# AdControl.net
KiCad netlist of a schematic drawn in Altium Designer
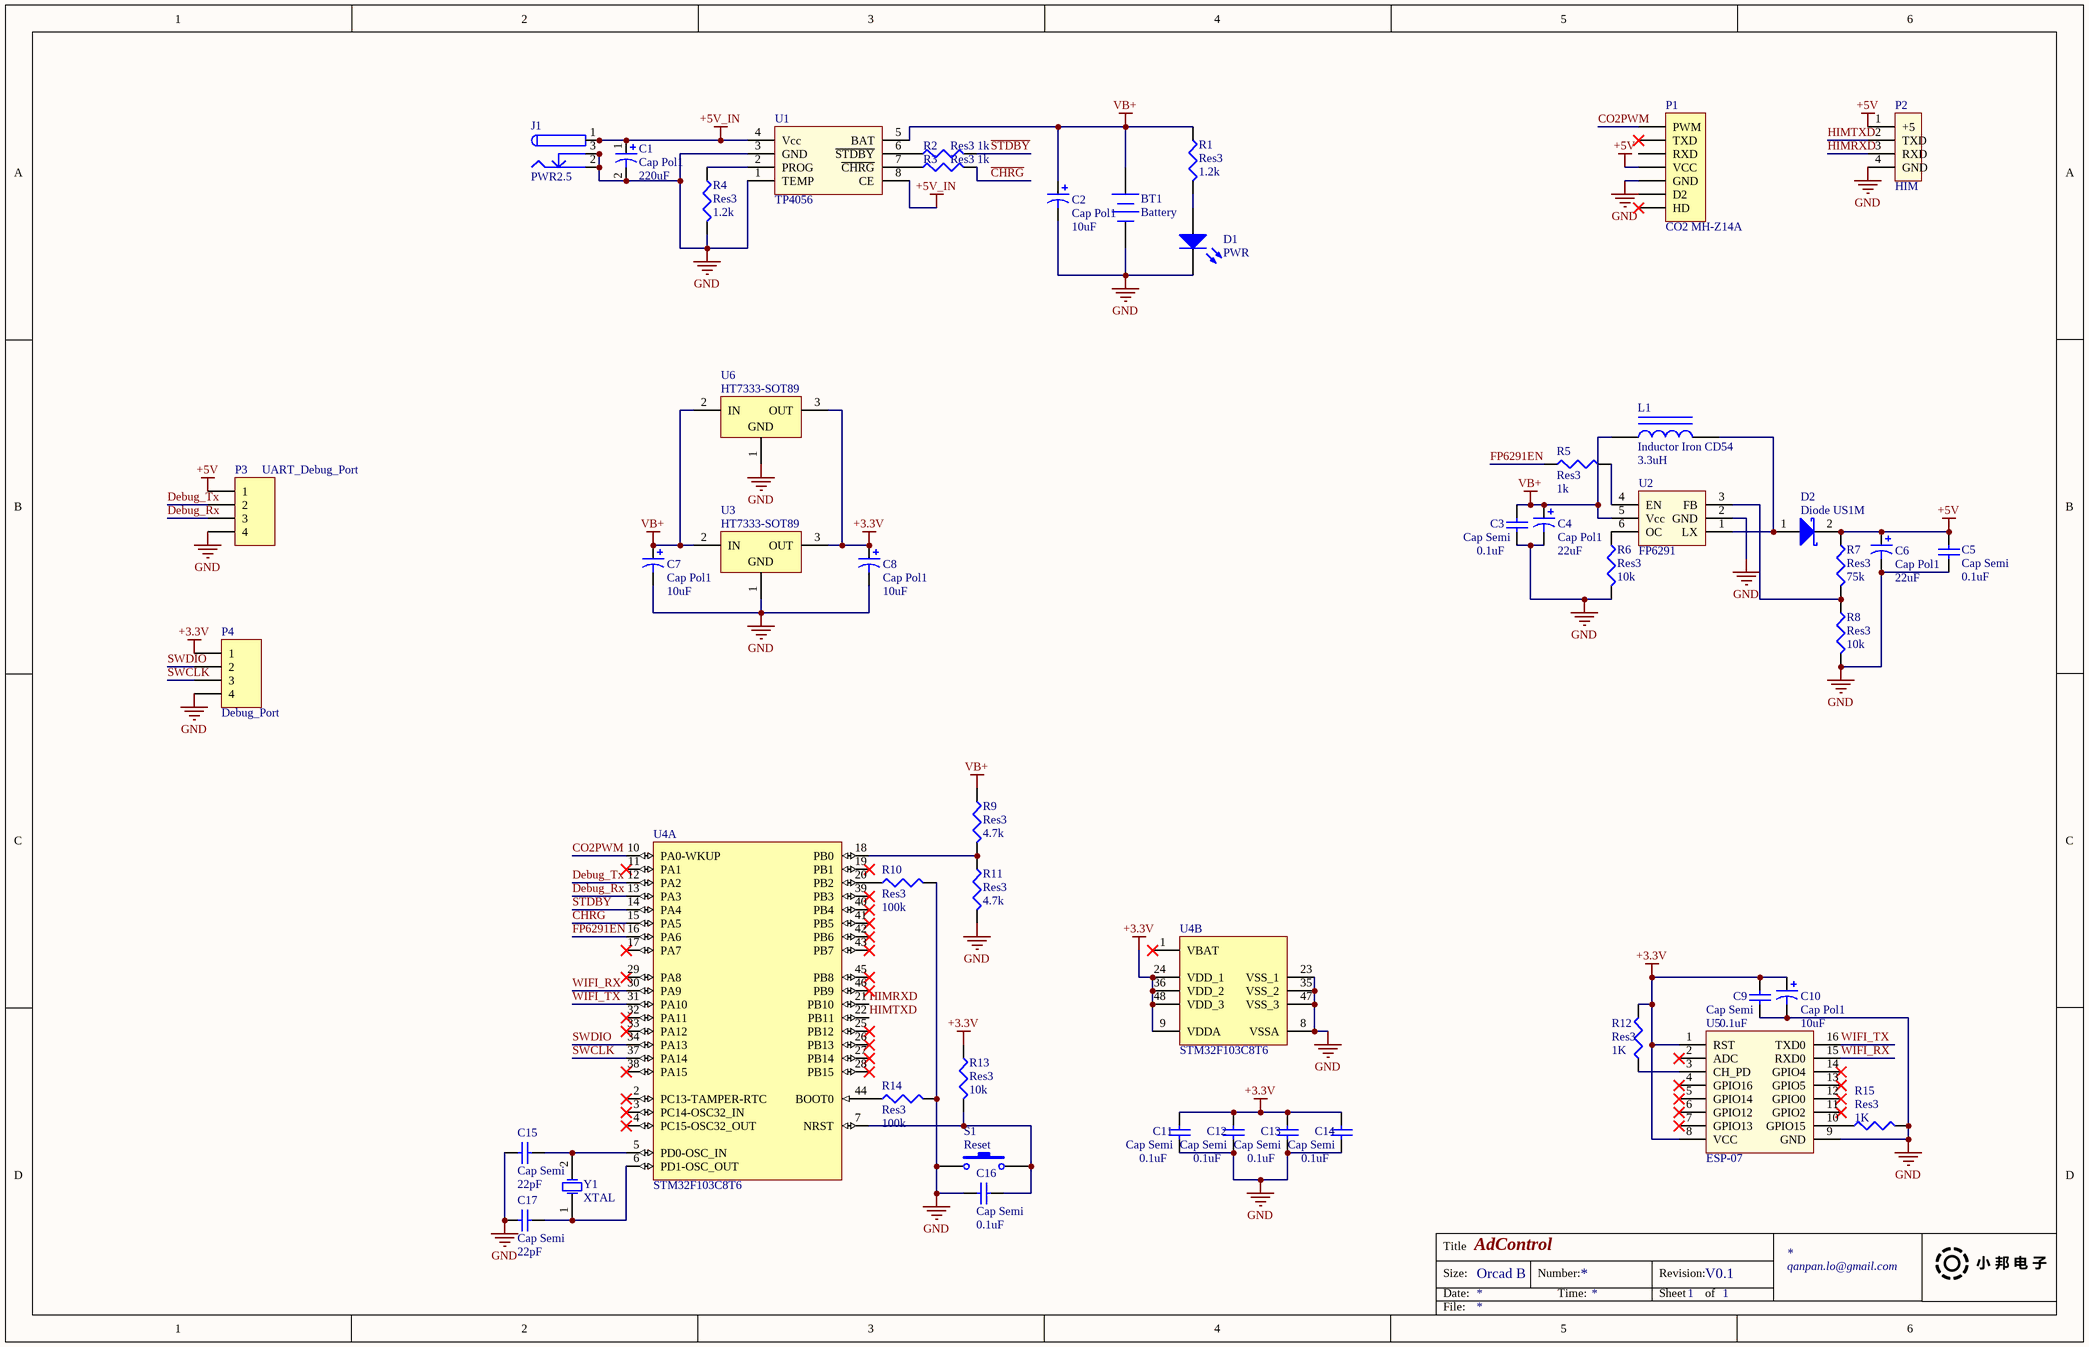
[diagram p0: AdControl.SchDoc]

(export (version "E")
  (design (tool "Eeschema 10.0.6"))
  (components
    (comp (ref "BT1")
      (value "Battery")
      (footprint "KF3.96_2P")
      (description "Multicell Battery")
      (fields (field (name "PUBLISHER") "Altium Limited"))
      (libsource (lib "Miscellaneous Devices") (part "Battery"))
    )
    (comp (ref "C1")
      (value "Cap Pol1")
      (footprint "CAP_6.3*5.4MM")
      (description "Polarized Capacitor (Radial)")
      (fields (field (name "ALTIUM_VALUE") "220uF") (field (name "PUBLISHER") "Altium Limited"))
      (libsource (lib "") (part "Cap Pol1_1"))
    )
    (comp (ref "C2")
      (value "Cap Pol1")
      (footprint "Cap_5*4mm")
      (description "Polarized Capacitor (Radial)")
      (fields (field (name "ALTIUM_VALUE") "10uF") (field (name "PUBLISHER") "Altium Limited"))
      (libsource (lib "Miscellaneous Devices") (part "Cap Pol1"))
    )
    (comp (ref "C3")
      (value "Cap Semi")
      (footprint "6-0805_N")
      (description "Capacitor (Semiconductor SIM Model)")
      (fields (field (name "ALTIUM_VALUE") "0.1uF") (field (name "PUBLISHER") "Altium Limited"))
      (libsource (lib "Miscellaneous Devices") (part "Cap Semi"))
    )
    (comp (ref "C4")
      (value "Cap Pol1")
      (footprint "Cap_5*4mm")
      (description "Polarized Capacitor (Radial)")
      (fields (field (name "ALTIUM_VALUE") "22uF") (field (name "PUBLISHER") "Altium Limited"))
      (libsource (lib "Miscellaneous Devices") (part "Cap Pol1"))
    )
    (comp (ref "C5")
      (value "Cap Semi")
      (footprint "6-0805_N")
      (description "Capacitor (Semiconductor SIM Model)")
      (fields (field (name "ALTIUM_VALUE") "0.1uF") (field (name "PUBLISHER") "Altium Limited"))
      (libsource (lib "Miscellaneous Devices") (part "Cap Semi"))
    )
    (comp (ref "C6")
      (value "Cap Pol1")
      (footprint "Cap_5*4mm")
      (description "Polarized Capacitor (Radial)")
      (fields (field (name "ALTIUM_VALUE") "22uF") (field (name "PUBLISHER") "Altium Limited"))
      (libsource (lib "Miscellaneous Devices") (part "Cap Pol1"))
    )
    (comp (ref "C7")
      (value "Cap Pol1")
      (footprint "Cap_5*4mm")
      (description "Polarized Capacitor (Radial)")
      (fields (field (name "ALTIUM_VALUE") "10uF") (field (name "PUBLISHER") "Altium Limited"))
      (libsource (lib "Miscellaneous Devices") (part "Cap Pol1"))
    )
    (comp (ref "C8")
      (value "Cap Pol1")
      (footprint "Cap_5*4mm")
      (description "Polarized Capacitor (Radial)")
      (fields (field (name "ALTIUM_VALUE") "10uF") (field (name "PUBLISHER") "Altium Limited"))
      (libsource (lib "Miscellaneous Devices") (part "Cap Pol1"))
    )
    (comp (ref "C9")
      (value "Cap Semi")
      (footprint "6-0805_N")
      (description "Capacitor (Semiconductor SIM Model)")
      (fields (field (name "ALTIUM_VALUE") "0.1uF") (field (name "PUBLISHER") "Altium Limited"))
      (libsource (lib "Miscellaneous Devices") (part "Cap Semi"))
    )
    (comp (ref "C10")
      (value "Cap Pol1")
      (footprint "Cap_5*4mm")
      (description "Polarized Capacitor (Radial)")
      (fields (field (name "ALTIUM_VALUE") "10uF") (field (name "PUBLISHER") "Altium Limited"))
      (libsource (lib "Miscellaneous Devices") (part "Cap Pol1"))
    )
    (comp (ref "C11")
      (value "Cap Semi")
      (footprint "6-0805_N")
      (description "Capacitor (Semiconductor SIM Model)")
      (fields (field (name "ALTIUM_VALUE") "0.1uF") (field (name "PUBLISHER") "Altium Limited"))
      (libsource (lib "Miscellaneous Devices") (part "Cap Semi"))
    )
    (comp (ref "C12")
      (value "Cap Semi")
      (footprint "6-0805_N")
      (description "Capacitor (Semiconductor SIM Model)")
      (fields (field (name "ALTIUM_VALUE") "0.1uF") (field (name "PUBLISHER") "Altium Limited"))
      (libsource (lib "Miscellaneous Devices") (part "Cap Semi"))
    )
    (comp (ref "C13")
      (value "Cap Semi")
      (footprint "6-0805_N")
      (description "Capacitor (Semiconductor SIM Model)")
      (fields (field (name "ALTIUM_VALUE") "0.1uF") (field (name "PUBLISHER") "Altium Limited"))
      (libsource (lib "Miscellaneous Devices") (part "Cap Semi"))
    )
    (comp (ref "C14")
      (value "Cap Semi")
      (footprint "6-0805_N")
      (description "Capacitor (Semiconductor SIM Model)")
      (fields (field (name "ALTIUM_VALUE") "0.1uF") (field (name "PUBLISHER") "Altium Limited"))
      (libsource (lib "Miscellaneous Devices") (part "Cap Semi"))
    )
    (comp (ref "C15")
      (value "Cap Semi")
      (footprint "6-0805_N")
      (description "Capacitor (Semiconductor SIM Model)")
      (fields (field (name "ALTIUM_VALUE") "22pF") (field (name "PUBLISHER") "Altium Limited"))
      (libsource (lib "Miscellaneous Devices") (part "Cap Semi"))
    )
    (comp (ref "C16")
      (value "Cap Semi")
      (footprint "6-0805_N")
      (description "Capacitor (Semiconductor SIM Model)")
      (fields (field (name "ALTIUM_VALUE") "0.1uF") (field (name "PUBLISHER") "Altium Limited"))
      (libsource (lib "Miscellaneous Devices") (part "Cap Semi"))
    )
    (comp (ref "C17")
      (value "Cap Semi")
      (footprint "6-0805_N")
      (description "Capacitor (Semiconductor SIM Model)")
      (fields (field (name "ALTIUM_VALUE") "22pF") (field (name "PUBLISHER") "Altium Limited"))
      (libsource (lib "Miscellaneous Devices") (part "Cap Semi"))
    )
    (comp (ref "D1")
      (value "PWR")
      (footprint "6-0805_N")
      (description "Typical INFRARED GaAs LED")
      (fields (field (name "PUBLISHER") "Altium Limited"))
      (libsource (lib "Miscellaneous Devices") (part "LED0"))
    )
    (comp (ref "D2")
      (value "Diode US1M")
      (footprint "US1M")
      (description "Silicon RF Schottky Diode for Mixer Applications in the VHF/UHF Range")
      (fields (field (name "PUBLISHER") "Altium Limited"))
      (libsource (lib "Miscellaneous Devices") (part "Diode BAT17"))
    )
    (comp (ref "J1")
      (value "PWR2.5")
      (footprint "KLD-3.5-1.3mm")
      (description "Low Voltage Power Supply Connector")
      (fields (field (name "PUBLISHER") "Altium Limited"))
      (libsource (lib "Miscellaneous Connectors") (part "PWR2.5"))
    )
    (comp (ref "L1")
      (value "Inductor Iron CD54")
      (footprint "CD54_Inductor")
      (description "Magnetic-Core Inductor")
      (fields (field (name "ALTIUM_VALUE") "3.3uH") (field (name "PUBLISHER") "Altium Limited"))
      (libsource (lib "Miscellaneous Devices") (part "Inductor Iron"))
    )
    (comp (ref "P1")
      (value "CO2 MH-Z14A")
      (footprint "1.25Connector")
      (description "Header, 7-Pin")
      (fields (field (name "PUBLISHER") "Altium Limited"))
      (libsource (lib "Miscellaneous Connectors") (part "Header 7"))
    )
    (comp (ref "P2") (value "HIM") (footprint "XH2.54-4P") (libsource (lib "XH2.54") (part "XH2.54-4P")))
    (comp (ref "P3")
      (value "UART_Debug_Port")
      (footprint "HDR1X4")
      (description "Header, 4-Pin")
      (fields (field (name "PUBLISHER") "Altium Limited"))
      (libsource (lib "Miscellaneous Connectors") (part "Header 4"))
    )
    (comp (ref "P4")
      (value "Debug_Port")
      (footprint "HDR1X4")
      (description "Header, 4-Pin")
      (fields (field (name "PUBLISHER") "Altium Limited"))
      (libsource (lib "Miscellaneous Connectors") (part "Header 4"))
    )
    (comp (ref "R1")
      (value "Res3")
      (footprint "6-0805_N")
      (description "Resistor")
      (fields (field (name "ALTIUM_VALUE") "1.2k") (field (name "PUBLISHER") "Altium Limited"))
      (libsource (lib "Miscellaneous Devices") (part "Res3"))
    )
    (comp (ref "R2")
      (value "Res3")
      (footprint "6-0805_N")
      (description "Resistor")
      (fields (field (name "ALTIUM_VALUE") "1k") (field (name "PUBLISHER") "Altium Limited"))
      (libsource (lib "Miscellaneous Devices") (part "Res3"))
    )
    (comp (ref "R3")
      (value "Res3")
      (footprint "6-0805_N")
      (description "Resistor")
      (fields (field (name "ALTIUM_VALUE") "1k") (field (name "PUBLISHER") "Altium Limited"))
      (libsource (lib "Miscellaneous Devices") (part "Res3"))
    )
    (comp (ref "R4")
      (value "Res3")
      (footprint "6-0805_N")
      (description "Resistor")
      (fields (field (name "ALTIUM_VALUE") "1.2k") (field (name "PUBLISHER") "Altium Limited"))
      (libsource (lib "Miscellaneous Devices") (part "Res3"))
    )
    (comp (ref "R5")
      (value "Res3")
      (footprint "6-0805_N")
      (description "Resistor")
      (fields (field (name "ALTIUM_VALUE") "1k") (field (name "PUBLISHER") "Altium Limited"))
      (libsource (lib "Miscellaneous Devices") (part "Res3"))
    )
    (comp (ref "R6")
      (value "Res3")
      (footprint "6-0805_N")
      (description "Resistor")
      (fields (field (name "ALTIUM_VALUE") "10k") (field (name "PUBLISHER") "Altium Limited"))
      (libsource (lib "Miscellaneous Devices") (part "Res3"))
    )
    (comp (ref "R7")
      (value "Res3")
      (footprint "6-0805_N")
      (description "Resistor")
      (fields (field (name "ALTIUM_VALUE") "75k") (field (name "PUBLISHER") "Altium Limited"))
      (libsource (lib "Miscellaneous Devices") (part "Res3"))
    )
    (comp (ref "R8")
      (value "Res3")
      (footprint "6-0805_N")
      (description "Resistor")
      (fields (field (name "ALTIUM_VALUE") "10k") (field (name "PUBLISHER") "Altium Limited"))
      (libsource (lib "Miscellaneous Devices") (part "Res3"))
    )
    (comp (ref "R9")
      (value "Res3")
      (footprint "6-0805_N")
      (description "Resistor")
      (fields (field (name "ALTIUM_VALUE") "4.7k") (field (name "PUBLISHER") "Altium Limited"))
      (libsource (lib "Miscellaneous Devices") (part "Res3"))
    )
    (comp (ref "R10")
      (value "Res3")
      (footprint "6-0805_N")
      (description "Resistor")
      (fields (field (name "ALTIUM_VALUE") "100k") (field (name "PUBLISHER") "Altium Limited"))
      (libsource (lib "Miscellaneous Devices") (part "Res3"))
    )
    (comp (ref "R11")
      (value "Res3")
      (footprint "6-0805_N")
      (description "Resistor")
      (fields (field (name "ALTIUM_VALUE") "4.7k") (field (name "PUBLISHER") "Altium Limited"))
      (libsource (lib "Miscellaneous Devices") (part "Res3"))
    )
    (comp (ref "R12")
      (value "Res3")
      (footprint "6-0805_N")
      (description "Resistor")
      (fields (field (name "ALTIUM_VALUE") "1K") (field (name "PUBLISHER") "Altium Limited"))
      (libsource (lib "Miscellaneous Devices") (part "Res3"))
    )
    (comp (ref "R13")
      (value "Res3")
      (footprint "6-0805_N")
      (description "Resistor")
      (fields (field (name "ALTIUM_VALUE") "10k") (field (name "PUBLISHER") "Altium Limited"))
      (libsource (lib "Miscellaneous Devices") (part "Res3"))
    )
    (comp (ref "R14")
      (value "Res3")
      (footprint "6-0805_N")
      (description "Resistor")
      (fields (field (name "ALTIUM_VALUE") "100k") (field (name "PUBLISHER") "Altium Limited"))
      (libsource (lib "Miscellaneous Devices") (part "Res3"))
    )
    (comp (ref "R15")
      (value "Res3")
      (footprint "6-0805_N")
      (description "Resistor")
      (fields (field (name "ALTIUM_VALUE") "1K") (field (name "PUBLISHER") "Altium Limited"))
      (libsource (lib "Miscellaneous Devices") (part "Res3"))
    )
    (comp (ref "S1")
      (value "Reset")
      (footprint "SWP_PB_6.5mm")
      (description "Switch")
      (fields (field (name "PUBLISHER") "Altium Limited"))
      (libsource (lib "Miscellaneous Devices") (part "SW-PB"))
    )
    (comp (ref "U1")
      (value "TP4056")
      (footprint "Power_SOP8")
      (libsource (lib "Simon'Library") (part "TP4056"))
    )
    (comp (ref "U2")
      (value "FP6291")
      (footprint "SOT23-6L")
      (libsource (lib "Simon'Library") (part "FP6291"))
    )
    (comp (ref "U3")
      (value "HT7333-SOT89")
      (footprint "SOT89_N")
      (description "Low Power Consumption LDO, Output Voltage 3.3V, SOT89 Pkg")
      (libsource (lib "Altium Content Vault") (part "PM-REG-HT73XX-IL3"))
    )
    (comp (ref "U4")
      (value "STM32F103C8T6")
      (footprint "STM-LQFP48_L")
      (libsource (lib "Altium Content Vault") (part "MC-ARM-STM32F103X8_B-SQ48"))
    )
    (comp (ref "U5")
      (value "ESP-07")
      (footprint "ESP-07_Wifi")
      (libsource (lib "Simon'Library") (part "ESP-07_Wifi"))
    )
    (comp (ref "U6")
      (value "HT7333-SOT89")
      (footprint "SOT89_N")
      (description "Low Power Consumption LDO, Output Voltage 3.3V, SOT89 Pkg")
      (libsource (lib "Altium Content Vault") (part "PM-REG-HT73XX-IL3"))
    )
    (comp (ref "Y1")
      (value "XTAL")
      (footprint "OSC_5032_2Pin")
      (description "Crystal Oscillator")
      (fields (field (name "PUBLISHER") "Altium Limited"))
      (libsource (lib "Miscellaneous Devices") (part "XTAL"))
    )
  )
  (nets
    (net (code "1") (name "+3.3V") (class "Default")
      (node (ref "C10") (pin "1") (pinfunction "1_1") (pintype "passive"))
      (node (ref "C11") (pin "1") (pinfunction "1_1") (pintype "passive"))
      (node (ref "C12") (pin "1") (pinfunction "1_1") (pintype "passive"))
      (node (ref "C13") (pin "1") (pinfunction "1_1") (pintype "passive"))
      (node (ref "C14") (pin "1") (pinfunction "1_1") (pintype "passive"))
      (node (ref "C8") (pin "1") (pinfunction "1_1") (pintype "passive"))
      (node (ref "C9") (pin "1") (pinfunction "1_1") (pintype "passive"))
      (node (ref "P4") (pin "1") (pinfunction "1_1") (pintype "passive"))
      (node (ref "R12") (pin "2") (pinfunction "2_2") (pintype "passive"))
      (node (ref "R13") (pin "1") (pinfunction "1_1") (pintype "passive"))
      (node (ref "U3") (pin "3") (pinfunction "OUT_3") (pintype "power_in"))
      (node (ref "U4") (pin "24") (pinfunction "VDD_1_24") (pintype "power_in"))
      (node (ref "U4") (pin "36") (pinfunction "VDD_2_36") (pintype "power_in"))
      (node (ref "U4") (pin "48") (pinfunction "VDD_3_48") (pintype "power_in"))
      (node (ref "U4") (pin "9") (pinfunction "VDDA_9") (pintype "power_in"))
      (node (ref "U5") (pin "1") (pinfunction "RST_1") (pintype "passive"))
      (node (ref "U5") (pin "8") (pinfunction "VCC_8") (pintype "passive"))
      (node (ref "U6") (pin "3") (pinfunction "OUT_3") (pintype "power_in"))
    )
    (net (code "2") (name "+5V") (class "Default")
      (node (ref "C5") (pin "1") (pinfunction "1_1") (pintype "passive"))
      (node (ref "C6") (pin "1") (pinfunction "1_1") (pintype "passive"))
      (node (ref "D2") (pin "2") (pinfunction "K_2") (pintype "passive"))
      (node (ref "P1") (pin "4") (pinfunction "VCC_4") (pintype "passive"))
      (node (ref "P2") (pin "1") (pinfunction "+5_1") (pintype "passive"))
      (node (ref "P3") (pin "1") (pinfunction "1_1") (pintype "passive"))
      (node (ref "R7") (pin "1") (pinfunction "1_1") (pintype "passive"))
    )
    (net (code "3") (name "+5V_IN") (class "Default")
      (node (ref "C1") (pin "1") (pinfunction "1_1") (pintype "passive"))
      (node (ref "J1") (pin "1") (pinfunction "1_1") (pintype "power_in"))
      (node (ref "J1") (pin "1A") (pinfunction "1A_1A") (pintype "power_in"))
      (node (ref "J1") (pin "1B") (pinfunction "1B_1B") (pintype "power_in"))
      (node (ref "U1") (pin "4") (pinfunction "Vcc_4") (pintype "passive"))
      (node (ref "U1") (pin "8") (pinfunction "CE_8") (pintype "passive"))
    )
    (net (code "4") (name "/CO2PWM") (class "Default")
      (node (ref "P1") (pin "1") (pinfunction "PWM_1") (pintype "passive"))
      (node (ref "U4") (pin "10") (pinfunction "PA0-WKUP_10") (pintype "bidirectional"))
    )
    (net (code "5") (name "/Debug_Rx") (class "Default")
      (node (ref "P3") (pin "3") (pinfunction "3_3") (pintype "passive"))
      (node (ref "U4") (pin "13") (pinfunction "PA3_13") (pintype "bidirectional"))
    )
    (net (code "6") (name "/Debug_Tx") (class "Default")
      (node (ref "P3") (pin "2") (pinfunction "2_2") (pintype "passive"))
      (node (ref "U4") (pin "12") (pinfunction "PA2_12") (pintype "bidirectional"))
    )
    (net (code "7") (name "/FP6291EN") (class "Default")
      (node (ref "R5") (pin "1") (pinfunction "1_1") (pintype "passive"))
      (node (ref "U4") (pin "16") (pinfunction "PA6_16") (pintype "bidirectional"))
    )
    (net (code "8") (name "/HIMRXD") (class "Default")
      (node (ref "P2") (pin "3") (pinfunction "RXD_3") (pintype "passive"))
      (node (ref "U4") (pin "21") (pinfunction "PB10_21") (pintype "bidirectional"))
    )
    (net (code "9") (name "/HIMTXD") (class "Default")
      (node (ref "P2") (pin "2") (pinfunction "TXD_2") (pintype "passive"))
      (node (ref "U4") (pin "22") (pinfunction "PB11_22") (pintype "bidirectional"))
    )
    (net (code "10") (name "/SWCLK") (class "Default")
      (node (ref "P4") (pin "3") (pinfunction "3_3") (pintype "passive"))
      (node (ref "U4") (pin "37") (pinfunction "PA14_37") (pintype "bidirectional"))
    )
    (net (code "11") (name "/SWDIO") (class "Default")
      (node (ref "P4") (pin "2") (pinfunction "2_2") (pintype "passive"))
      (node (ref "U4") (pin "34") (pinfunction "PA13_34") (pintype "bidirectional"))
    )
    (net (code "12") (name "/WIFI_RX") (class "Default")
      (node (ref "U4") (pin "30") (pinfunction "PA9_30") (pintype "bidirectional"))
      (node (ref "U5") (pin "15") (pinfunction "RXD0_15") (pintype "passive"))
    )
    (net (code "13") (name "/WIFI_TX") (class "Default")
      (node (ref "U4") (pin "31") (pinfunction "PA10_31") (pintype "bidirectional"))
      (node (ref "U5") (pin "16") (pinfunction "TXD0_16") (pintype "passive"))
    )
    (net (code "14") (name "/~{CHRG}") (class "Default")
      (node (ref "R3") (pin "2") (pinfunction "2_2") (pintype "passive"))
      (node (ref "U4") (pin "15") (pinfunction "PA5_15") (pintype "bidirectional"))
    )
    (net (code "15") (name "/~{STDBY}") (class "Default")
      (node (ref "R2") (pin "2") (pinfunction "2_2") (pintype "passive"))
      (node (ref "U4") (pin "14") (pinfunction "PA4_14") (pintype "bidirectional"))
    )
    (net (code "16") (name "GND") (class "Default")
      (node (ref "BT1") (pin "2") (pinfunction "-_2") (pintype "passive"))
      (node (ref "C1") (pin "2") (pinfunction "2_2") (pintype "passive"))
      (node (ref "C10") (pin "2") (pinfunction "2_2") (pintype "passive"))
      (node (ref "C11") (pin "2") (pinfunction "2_2") (pintype "passive"))
      (node (ref "C12") (pin "2") (pinfunction "2_2") (pintype "passive"))
      (node (ref "C13") (pin "2") (pinfunction "2_2") (pintype "passive"))
      (node (ref "C14") (pin "2") (pinfunction "2_2") (pintype "passive"))
      (node (ref "C15") (pin "2") (pinfunction "2_2") (pintype "passive"))
      (node (ref "C16") (pin "1") (pinfunction "1_1") (pintype "passive"))
      (node (ref "C17") (pin "2") (pinfunction "2_2") (pintype "passive"))
      (node (ref "C2") (pin "2") (pinfunction "2_2") (pintype "passive"))
      (node (ref "C3") (pin "2") (pinfunction "2_2") (pintype "passive"))
      (node (ref "C4") (pin "2") (pinfunction "2_2") (pintype "passive"))
      (node (ref "C5") (pin "2") (pinfunction "2_2") (pintype "passive"))
      (node (ref "C6") (pin "2") (pinfunction "2_2") (pintype "passive"))
      (node (ref "C7") (pin "2") (pinfunction "2_2") (pintype "passive"))
      (node (ref "C8") (pin "2") (pinfunction "2_2") (pintype "passive"))
      (node (ref "C9") (pin "2") (pinfunction "2_2") (pintype "passive"))
      (node (ref "D1") (pin "2") (pinfunction "K_2") (pintype "passive"))
      (node (ref "J1") (pin "2") (pinfunction "2_2") (pintype "power_in"))
      (node (ref "J1") (pin "2A") (pinfunction "2A_2A") (pintype "power_in"))
      (node (ref "J1") (pin "2B") (pinfunction "2B_2B") (pintype "power_in"))
      (node (ref "J1") (pin "3") (pinfunction "3_3") (pintype "power_in"))
      (node (ref "J1") (pin "3A") (pinfunction "3A_3A") (pintype "power_in"))
      (node (ref "J1") (pin "3B") (pinfunction "3B_3B") (pintype "power_in"))
      (node (ref "P1") (pin "5") (pinfunction "GND_5") (pintype "passive"))
      (node (ref "P2") (pin "4") (pinfunction "GND_4") (pintype "passive"))
      (node (ref "P3") (pin "4") (pinfunction "4_4") (pintype "passive"))
      (node (ref "P4") (pin "4") (pinfunction "4_4") (pintype "passive"))
      (node (ref "R10") (pin "2") (pinfunction "2_2") (pintype "passive"))
      (node (ref "R11") (pin "2") (pinfunction "2_2") (pintype "passive"))
      (node (ref "R14") (pin "2") (pinfunction "2_2") (pintype "passive"))
      (node (ref "R15") (pin "2") (pinfunction "2_2") (pintype "passive"))
      (node (ref "R4") (pin "2") (pinfunction "2_2") (pintype "passive"))
      (node (ref "R6") (pin "2") (pinfunction "2_2") (pintype "passive"))
      (node (ref "R8") (pin "2") (pinfunction "2_2") (pintype "passive"))
      (node (ref "S1") (pin "1") (pinfunction "1_1") (pintype "passive"))
      (node (ref "U1") (pin "1") (pinfunction "TEMP_1") (pintype "passive"))
      (node (ref "U1") (pin "3") (pinfunction "GND_3") (pintype "passive"))
      (node (ref "U2") (pin "2") (pinfunction "GND_2") (pintype "passive"))
      (node (ref "U3") (pin "1") (pinfunction "GND_1") (pintype "power_in"))
      (node (ref "U4") (pin "23") (pinfunction "VSS_1_23") (pintype "power_in"))
      (node (ref "U4") (pin "35") (pinfunction "VSS_2_35") (pintype "power_in"))
      (node (ref "U4") (pin "47") (pinfunction "VSS_3_47") (pintype "power_in"))
      (node (ref "U4") (pin "8") (pinfunction "VSSA_8") (pintype "power_in"))
      (node (ref "U5") (pin "9") (pinfunction "GND_9") (pintype "passive"))
      (node (ref "U6") (pin "1") (pinfunction "GND_1") (pintype "power_in"))
    )
    (net (code "17") (name "Net-(D1-A)") (class "Default")
      (node (ref "D1") (pin "1") (pinfunction "A_1") (pintype "passive"))
      (node (ref "R1") (pin "2") (pinfunction "2_2") (pintype "passive"))
    )
    (net (code "18") (name "Net-(D2-A)") (class "Default")
      (node (ref "D2") (pin "1") (pinfunction "A_1") (pintype "passive"))
      (node (ref "L1") (pin "2") (pinfunction "2_2") (pintype "passive"))
      (node (ref "U2") (pin "1") (pinfunction "LX_1") (pintype "passive"))
    )
    (net (code "19") (name "Net-(U1-PROG)") (class "Default")
      (node (ref "R4") (pin "1") (pinfunction "1_1") (pintype "passive"))
      (node (ref "U1") (pin "2") (pinfunction "PROG_2") (pintype "passive"))
    )
    (net (code "20") (name "Net-(U1-~{CHRG})") (class "Default")
      (node (ref "R3") (pin "1") (pinfunction "1_1") (pintype "passive"))
      (node (ref "U1") (pin "7") (pinfunction "~{CHRG}_7") (pintype "passive"))
    )
    (net (code "21") (name "Net-(U1-~{STDBY})") (class "Default")
      (node (ref "R2") (pin "1") (pinfunction "1_1") (pintype "passive"))
      (node (ref "U1") (pin "6") (pinfunction "~{STDBY}_6") (pintype "passive"))
    )
    (net (code "22") (name "Net-(U2-EN)") (class "Default")
      (node (ref "R5") (pin "2") (pinfunction "2_2") (pintype "passive"))
      (node (ref "U2") (pin "4") (pinfunction "EN_4") (pintype "passive"))
    )
    (net (code "23") (name "Net-(U2-FB)") (class "Default")
      (node (ref "R7") (pin "2") (pinfunction "2_2") (pintype "passive"))
      (node (ref "R8") (pin "1") (pinfunction "1_1") (pintype "passive"))
      (node (ref "U2") (pin "3") (pinfunction "FB_3") (pintype "passive"))
    )
    (net (code "24") (name "Net-(U2-OC)") (class "Default")
      (node (ref "R6") (pin "1") (pinfunction "1_1") (pintype "passive"))
      (node (ref "U2") (pin "6") (pinfunction "OC_6") (pintype "passive"))
    )
    (net (code "25") (name "Net-(U4A-BOOT0)") (class "Default")
      (node (ref "R14") (pin "1") (pinfunction "1_1") (pintype "passive"))
      (node (ref "U4") (pin "44") (pinfunction "BOOT0_44") (pintype "input"))
    )
    (net (code "26") (name "Net-(U4A-NRST)") (class "Default")
      (node (ref "C16") (pin "2") (pinfunction "2_2") (pintype "passive"))
      (node (ref "R13") (pin "2") (pinfunction "2_2") (pintype "passive"))
      (node (ref "S1") (pin "2") (pinfunction "2_2") (pintype "passive"))
      (node (ref "U4") (pin "7") (pinfunction "NRST_7") (pintype "bidirectional"))
    )
    (net (code "27") (name "Net-(U4A-PB0)") (class "Default")
      (node (ref "R11") (pin "1") (pinfunction "1_1") (pintype "passive"))
      (node (ref "R9") (pin "2") (pinfunction "2_2") (pintype "passive"))
      (node (ref "U4") (pin "18") (pinfunction "PB0_18") (pintype "bidirectional"))
    )
    (net (code "28") (name "Net-(U4A-PB2)") (class "Default")
      (node (ref "R10") (pin "1") (pinfunction "1_1") (pintype "passive"))
      (node (ref "U4") (pin "20") (pinfunction "PB2_20") (pintype "bidirectional"))
    )
    (net (code "29") (name "Net-(U4A-PD0-OSC_IN)") (class "Default")
      (node (ref "C15") (pin "1") (pinfunction "1_1") (pintype "passive"))
      (node (ref "U4") (pin "5") (pinfunction "PD0-OSC_IN_5") (pintype "bidirectional"))
      (node (ref "Y1") (pin "2") (pinfunction "OSC2_2") (pintype "passive"))
    )
    (net (code "30") (name "Net-(U4A-PD1-OSC_OUT)") (class "Default")
      (node (ref "C17") (pin "1") (pinfunction "1_1") (pintype "passive"))
      (node (ref "U4") (pin "6") (pinfunction "PD1-OSC_OUT_6") (pintype "bidirectional"))
      (node (ref "Y1") (pin "1") (pinfunction "OSC1_1") (pintype "passive"))
    )
    (net (code "31") (name "Net-(U5-CH_PD)") (class "Default")
      (node (ref "R12") (pin "1") (pinfunction "1_1") (pintype "passive"))
      (node (ref "U5") (pin "3") (pinfunction "CH_PD_3") (pintype "passive"))
    )
    (net (code "32") (name "Net-(U5-GPIO15)") (class "Default")
      (node (ref "R15") (pin "1") (pinfunction "1_1") (pintype "passive"))
      (node (ref "U5") (pin "10") (pinfunction "GPIO15_10") (pintype "passive"))
    )
    (net (code "33") (name "VB+") (class "Default")
      (node (ref "BT1") (pin "1") (pinfunction "+_1") (pintype "passive"))
      (node (ref "C2") (pin "1") (pinfunction "1_1") (pintype "passive"))
      (node (ref "C3") (pin "1") (pinfunction "1_1") (pintype "passive"))
      (node (ref "C4") (pin "1") (pinfunction "1_1") (pintype "passive"))
      (node (ref "C7") (pin "1") (pinfunction "1_1") (pintype "passive"))
      (node (ref "L1") (pin "1") (pinfunction "1_1") (pintype "passive"))
      (node (ref "R1") (pin "1") (pinfunction "1_1") (pintype "passive"))
      (node (ref "R9") (pin "1") (pinfunction "1_1") (pintype "passive"))
      (node (ref "U1") (pin "5") (pinfunction "BAT_5") (pintype "passive"))
      (node (ref "U2") (pin "5") (pinfunction "Vcc_5") (pintype "passive"))
      (node (ref "U3") (pin "2") (pinfunction "IN_2") (pintype "power_in"))
      (node (ref "U6") (pin "2") (pinfunction "IN_2") (pintype "power_in"))
    )
    (net (code "34") (name "unconnected-(P1-D2-Pad6)") (class "Default")
      (node (ref "P1") (pin "6") (pinfunction "D2_6") (pintype "passive"))
    )
    (net (code "35") (name "unconnected-(P1-HD-Pad7)") (class "Default")
      (node (ref "P1") (pin "7") (pinfunction "HD_7") (pintype "passive+no_connect"))
    )
    (net (code "36") (name "unconnected-(P1-RXD-Pad3)") (class "Default")
      (node (ref "P1") (pin "3") (pinfunction "RXD_3") (pintype "passive"))
    )
    (net (code "37") (name "unconnected-(P1-TXD-Pad2)") (class "Default")
      (node (ref "P1") (pin "2") (pinfunction "TXD_2") (pintype "passive+no_connect"))
    )
    (net (code "38") (name "unconnected-(U4A-PA1-Pad11)") (class "Default")
      (node (ref "U4") (pin "11") (pinfunction "PA1_11") (pintype "bidirectional+no_connect"))
    )
    (net (code "39") (name "unconnected-(U4A-PA7-Pad17)") (class "Default")
      (node (ref "U4") (pin "17") (pinfunction "PA7_17") (pintype "bidirectional+no_connect"))
    )
    (net (code "40") (name "unconnected-(U4A-PA8-Pad29)") (class "Default")
      (node (ref "U4") (pin "29") (pinfunction "PA8_29") (pintype "bidirectional+no_connect"))
    )
    (net (code "41") (name "unconnected-(U4A-PA11-Pad32)") (class "Default")
      (node (ref "U4") (pin "32") (pinfunction "PA11_32") (pintype "bidirectional+no_connect"))
    )
    (net (code "42") (name "unconnected-(U4A-PA12-Pad33)") (class "Default")
      (node (ref "U4") (pin "33") (pinfunction "PA12_33") (pintype "bidirectional+no_connect"))
    )
    (net (code "43") (name "unconnected-(U4A-PA15-Pad38)") (class "Default")
      (node (ref "U4") (pin "38") (pinfunction "PA15_38") (pintype "bidirectional+no_connect"))
    )
    (net (code "44") (name "unconnected-(U4A-PB1-Pad19)") (class "Default")
      (node (ref "U4") (pin "19") (pinfunction "PB1_19") (pintype "bidirectional+no_connect"))
    )
    (net (code "45") (name "unconnected-(U4A-PB3-Pad39)") (class "Default")
      (node (ref "U4") (pin "39") (pinfunction "PB3_39") (pintype "bidirectional+no_connect"))
    )
    (net (code "46") (name "unconnected-(U4A-PB4-Pad40)") (class "Default")
      (node (ref "U4") (pin "40") (pinfunction "PB4_40") (pintype "bidirectional+no_connect"))
    )
    (net (code "47") (name "unconnected-(U4A-PB5-Pad41)") (class "Default")
      (node (ref "U4") (pin "41") (pinfunction "PB5_41") (pintype "bidirectional+no_connect"))
    )
    (net (code "48") (name "unconnected-(U4A-PB6-Pad42)") (class "Default")
      (node (ref "U4") (pin "42") (pinfunction "PB6_42") (pintype "bidirectional+no_connect"))
    )
    (net (code "49") (name "unconnected-(U4A-PB7-Pad43)") (class "Default")
      (node (ref "U4") (pin "43") (pinfunction "PB7_43") (pintype "bidirectional+no_connect"))
    )
    (net (code "50") (name "unconnected-(U4A-PB8-Pad45)") (class "Default")
      (node (ref "U4") (pin "45") (pinfunction "PB8_45") (pintype "bidirectional+no_connect"))
    )
    (net (code "51") (name "unconnected-(U4A-PB9-Pad46)") (class "Default")
      (node (ref "U4") (pin "46") (pinfunction "PB9_46") (pintype "bidirectional+no_connect"))
    )
    (net (code "52") (name "unconnected-(U4A-PB12-Pad25)") (class "Default")
      (node (ref "U4") (pin "25") (pinfunction "PB12_25") (pintype "bidirectional+no_connect"))
    )
    (net (code "53") (name "unconnected-(U4A-PB13-Pad26)") (class "Default")
      (node (ref "U4") (pin "26") (pinfunction "PB13_26") (pintype "bidirectional+no_connect"))
    )
    (net (code "54") (name "unconnected-(U4A-PB14-Pad27)") (class "Default")
      (node (ref "U4") (pin "27") (pinfunction "PB14_27") (pintype "bidirectional+no_connect"))
    )
    (net (code "55") (name "unconnected-(U4A-PB15-Pad28)") (class "Default")
      (node (ref "U4") (pin "28") (pinfunction "PB15_28") (pintype "bidirectional+no_connect"))
    )
    (net (code "56") (name "unconnected-(U4A-PC13-TAMPER-RTC-Pad2)") (class "Default")
      (node (ref "U4") (pin "2") (pinfunction "PC13-TAMPER-RTC_2") (pintype "bidirectional+no_connect"))
    )
    (net (code "57") (name "unconnected-(U4A-PC14-OSC32_IN-Pad3)") (class "Default")
      (node (ref "U4") (pin "3") (pinfunction "PC14-OSC32_IN_3") (pintype "bidirectional+no_connect"))
    )
    (net (code "58") (name "unconnected-(U4A-PC15-OSC32_OUT-Pad4)") (class "Default")
      (node (ref "U4") (pin "4") (pinfunction "PC15-OSC32_OUT_4") (pintype "bidirectional+no_connect"))
    )
    (net (code "59") (name "unconnected-(U4B-VBAT-Pad1)") (class "Default")
      (node (ref "U4") (pin "1") (pinfunction "VBAT_1") (pintype "power_in+no_connect"))
    )
    (net (code "60") (name "unconnected-(U5-ADC-Pad2)") (class "Default")
      (node (ref "U5") (pin "2") (pinfunction "ADC_2") (pintype "passive+no_connect"))
    )
    (net (code "61") (name "unconnected-(U5-GPIO0-Pad12)") (class "Default")
      (node (ref "U5") (pin "12") (pinfunction "GPIO0_12") (pintype "passive+no_connect"))
    )
    (net (code "62") (name "unconnected-(U5-GPIO2-Pad11)") (class "Default")
      (node (ref "U5") (pin "11") (pinfunction "GPIO2_11") (pintype "passive+no_connect"))
    )
    (net (code "63") (name "unconnected-(U5-GPIO4-Pad14)") (class "Default")
      (node (ref "U5") (pin "14") (pinfunction "GPIO4_14") (pintype "passive+no_connect"))
    )
    (net (code "64") (name "unconnected-(U5-GPIO5-Pad13)") (class "Default")
      (node (ref "U5") (pin "13") (pinfunction "GPIO5_13") (pintype "passive+no_connect"))
    )
    (net (code "65") (name "unconnected-(U5-GPIO12-Pad6)") (class "Default")
      (node (ref "U5") (pin "6") (pinfunction "GPIO12_6") (pintype "passive+no_connect"))
    )
    (net (code "66") (name "unconnected-(U5-GPIO13-Pad7)") (class "Default")
      (node (ref "U5") (pin "7") (pinfunction "GPIO13_7") (pintype "passive+no_connect"))
    )
    (net (code "67") (name "unconnected-(U5-GPIO14-Pad5)") (class "Default")
      (node (ref "U5") (pin "5") (pinfunction "GPIO14_5") (pintype "passive+no_connect"))
    )
    (net (code "68") (name "unconnected-(U5-GPIO16-Pad4)") (class "Default")
      (node (ref "U5") (pin "4") (pinfunction "GPIO16_4") (pintype "passive+no_connect"))
    )
  )
)
